# DS153-1_0-C.net
KiCad netlist of a schematic drawn in Altium Designer
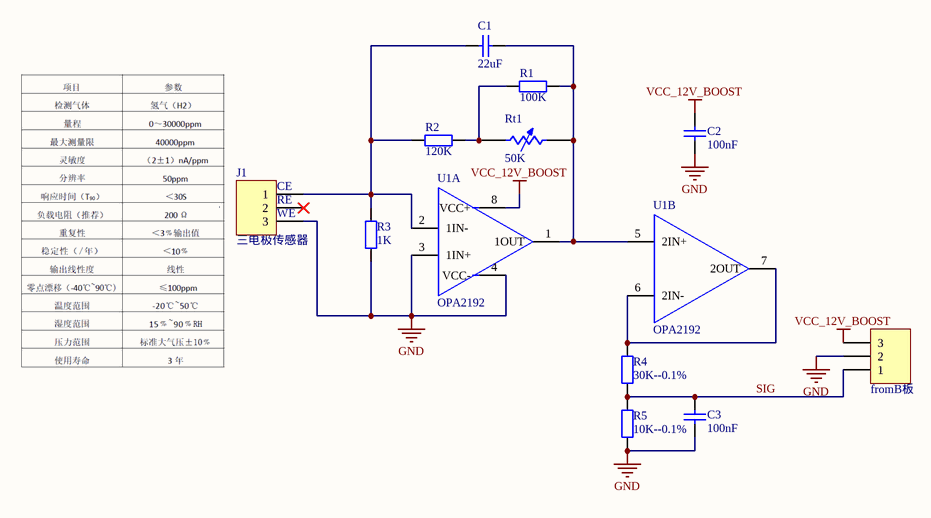
[diagram p0: DS153-1.0-C氢气传感器.SchDoc]

(export (version "E")
  (design (tool "Eeschema 10.0.6"))
  (components
    (comp (ref "1")
      (value "fromB板")
      (footprint "XH2.54-3P")
      (description "3P直针座")
      (fields (field (name "Comment") "SL000000028"))
      (libsource (lib "AD_SCH") (part "XH2.54mm-3A 直针座"))
    )
    (comp (ref "C1")
      (value "22uF")
      (footprint "1206CAP")
      (description "贴片电容")
      (fields (field (name "Comment") "MLCC 22uF 50V ±20％ 1206"))
      (libsource (lib "AD_SCH") (part "MLCC 22uF 50V ±20％ 1206"))
    )
    (comp (ref "C2")
      (value "100nF")
      (footprint "0603CAP")
      (description "贴片电容")
      (fields (field (name "Comment") "SMDCAP00013"))
      (libsource (lib "AD_SCH") (part "MLCC 100nF 50V ±10％ 0603"))
    )
    (comp (ref "C3")
      (value "100nF")
      (footprint "0603CAP")
      (description "贴片电容")
      (fields (field (name "Comment") "SMDCAP00013"))
      (libsource (lib "AD_SCH") (part "MLCC 100nF 50V ±10％ 0603"))
    )
    (comp (ref "J1")
      (value "三电极传感器")
      (footprint "2_Electrode")
      (description "单排直针")
      (fields (field (name "Comment") "SL000000042"))
      (libsource (lib "AD_SCH") (part "DIP3 单排直针 间距2.54mm 针长11mm 铜"))
    )
    (comp (ref "R1")
      (value "100K")
      (footprint "0603RES")
      (description "贴片电阻")
      (fields (field (name "Comment") "SMDRES00071"))
      (libsource (lib "AD_SCH") (part "Chip 100K 1/16W ±1％ 0603"))
    )
    (comp (ref "R2")
      (value "120K")
      (footprint "0603RES")
      (description "贴片电阻")
      (fields (field (name "Comment") "Chip 120K 1/16W ±1％ 0603"))
      (libsource (lib "AD_SCH") (part "Chip 120K 1/16W ±1％ 0603"))
    )
    (comp (ref "R3")
      (value "1K")
      (footprint "0603RES")
      (description "贴片电阻")
      (fields (field (name "Comment") "SMDRES00034"))
      (libsource (lib "AD_SCH") (part "Chip 1K 1/16W ±1％ 0603"))
    )
    (comp (ref "R4")
      (value "30K--0.1%")
      (footprint "0603RES")
      (description "贴片电阻")
      (fields (field (name "Comment") "SMDRES00060"))
      (libsource (lib "AD_SCH") (part "Chip 30K 1/16W ±1％ 0603"))
    )
    (comp (ref "R5")
      (value "10K--0.1%")
      (footprint "0603RES")
      (description "贴片电阻")
      (fields (field (name "Comment") "SMDRES00056"))
      (libsource (lib "AD_SCH") (part "Chip 10K 1/16W ±1％ 0603"))
    )
    (comp (ref "Rt1")
      (value "50K")
      (footprint "0603RES")
      (description "热敏电阻")
      (fields (field (name "Comment") "SE000000015"))
      (libsource (lib "AD_SCH") (part "NTC 10K 热敏电阻 5% Φ5 MF52A1 B值{colon}3950K"))
    )
    (comp (ref "U1") (value "OPA2192") (footprint "SO-8") (libsource (lib "AD_SCH") (part "TL062C")))
  )
  (nets
    (net (code "1") (name "/SIG") (class "Default")
      (node (ref "1") (pin "1") (pinfunction "1_1") (pintype "passive"))
      (node (ref "C3") (pin "2") (pinfunction "2_2") (pintype "passive"))
      (node (ref "R4") (pin "1") (pinfunction "1_1") (pintype "passive"))
      (node (ref "R5") (pin "2") (pinfunction "2_2") (pintype "passive"))
    )
    (net (code "2") (name "GND") (class "Default")
      (node (ref "1") (pin "2") (pinfunction "2_2") (pintype "passive"))
      (node (ref "C2") (pin "1") (pinfunction "1_1") (pintype "passive"))
      (node (ref "C3") (pin "1") (pinfunction "1_1") (pintype "passive"))
      (node (ref "J1") (pin "3") (pinfunction "3_3") (pintype "passive"))
      (node (ref "R3") (pin "1") (pinfunction "1_1") (pintype "passive"))
      (node (ref "R5") (pin "1") (pinfunction "1_1") (pintype "passive"))
      (node (ref "U1") (pin "3") (pinfunction "1IN+_3") (pintype "passive"))
      (node (ref "U1") (pin "4") (pinfunction "VCC-_4") (pintype "passive"))
    )
    (net (code "3") (name "Net-(R1-Pad1)") (class "Default")
      (node (ref "R1") (pin "1") (pinfunction "1_1") (pintype "passive"))
      (node (ref "R2") (pin "2") (pinfunction "2_2") (pintype "passive"))
      (node (ref "Rt1") (pin "2") (pinfunction "2_2") (pintype "passive"))
    )
    (net (code "4") (name "Net-(U1A-1IN-)") (class "Default")
      (node (ref "C1") (pin "1") (pinfunction "1_1") (pintype "passive"))
      (node (ref "J1") (pin "1") (pinfunction "1_1") (pintype "passive"))
      (node (ref "R2") (pin "1") (pinfunction "1_1") (pintype "passive"))
      (node (ref "R3") (pin "2") (pinfunction "2_2") (pintype "passive"))
      (node (ref "U1") (pin "2") (pinfunction "1IN-_2") (pintype "passive"))
    )
    (net (code "5") (name "Net-(U1A-1OUT)") (class "Default")
      (node (ref "C1") (pin "2") (pinfunction "2_2") (pintype "passive"))
      (node (ref "R1") (pin "2") (pinfunction "2_2") (pintype "passive"))
      (node (ref "Rt1") (pin "1") (pinfunction "1_1") (pintype "passive"))
      (node (ref "U1") (pin "1") (pinfunction "1OUT_1") (pintype "passive"))
      (node (ref "U1") (pin "5") (pinfunction "2IN+_5") (pintype "passive"))
    )
    (net (code "6") (name "Net-(U1B-2IN-)") (class "Default")
      (node (ref "R4") (pin "2") (pinfunction "2_2") (pintype "passive"))
      (node (ref "U1") (pin "6") (pinfunction "2IN-_6") (pintype "passive"))
      (node (ref "U1") (pin "7") (pinfunction "2OUT_7") (pintype "passive"))
    )
    (net (code "7") (name "VCC_12V_BOOST") (class "Default")
      (node (ref "1") (pin "3") (pinfunction "3_3") (pintype "passive"))
      (node (ref "C2") (pin "2") (pinfunction "2_2") (pintype "passive"))
      (node (ref "U1") (pin "8") (pinfunction "VCC+_8") (pintype "passive"))
    )
    (net (code "8") (name "unconnected-(J1-Pad2)") (class "Default")
      (node (ref "J1") (pin "2") (pinfunction "2_2") (pintype "passive+no_connect"))
    )
  )
)
